# Bridge_H.net
KiCad netlist of a schematic drawn in Altium Designer
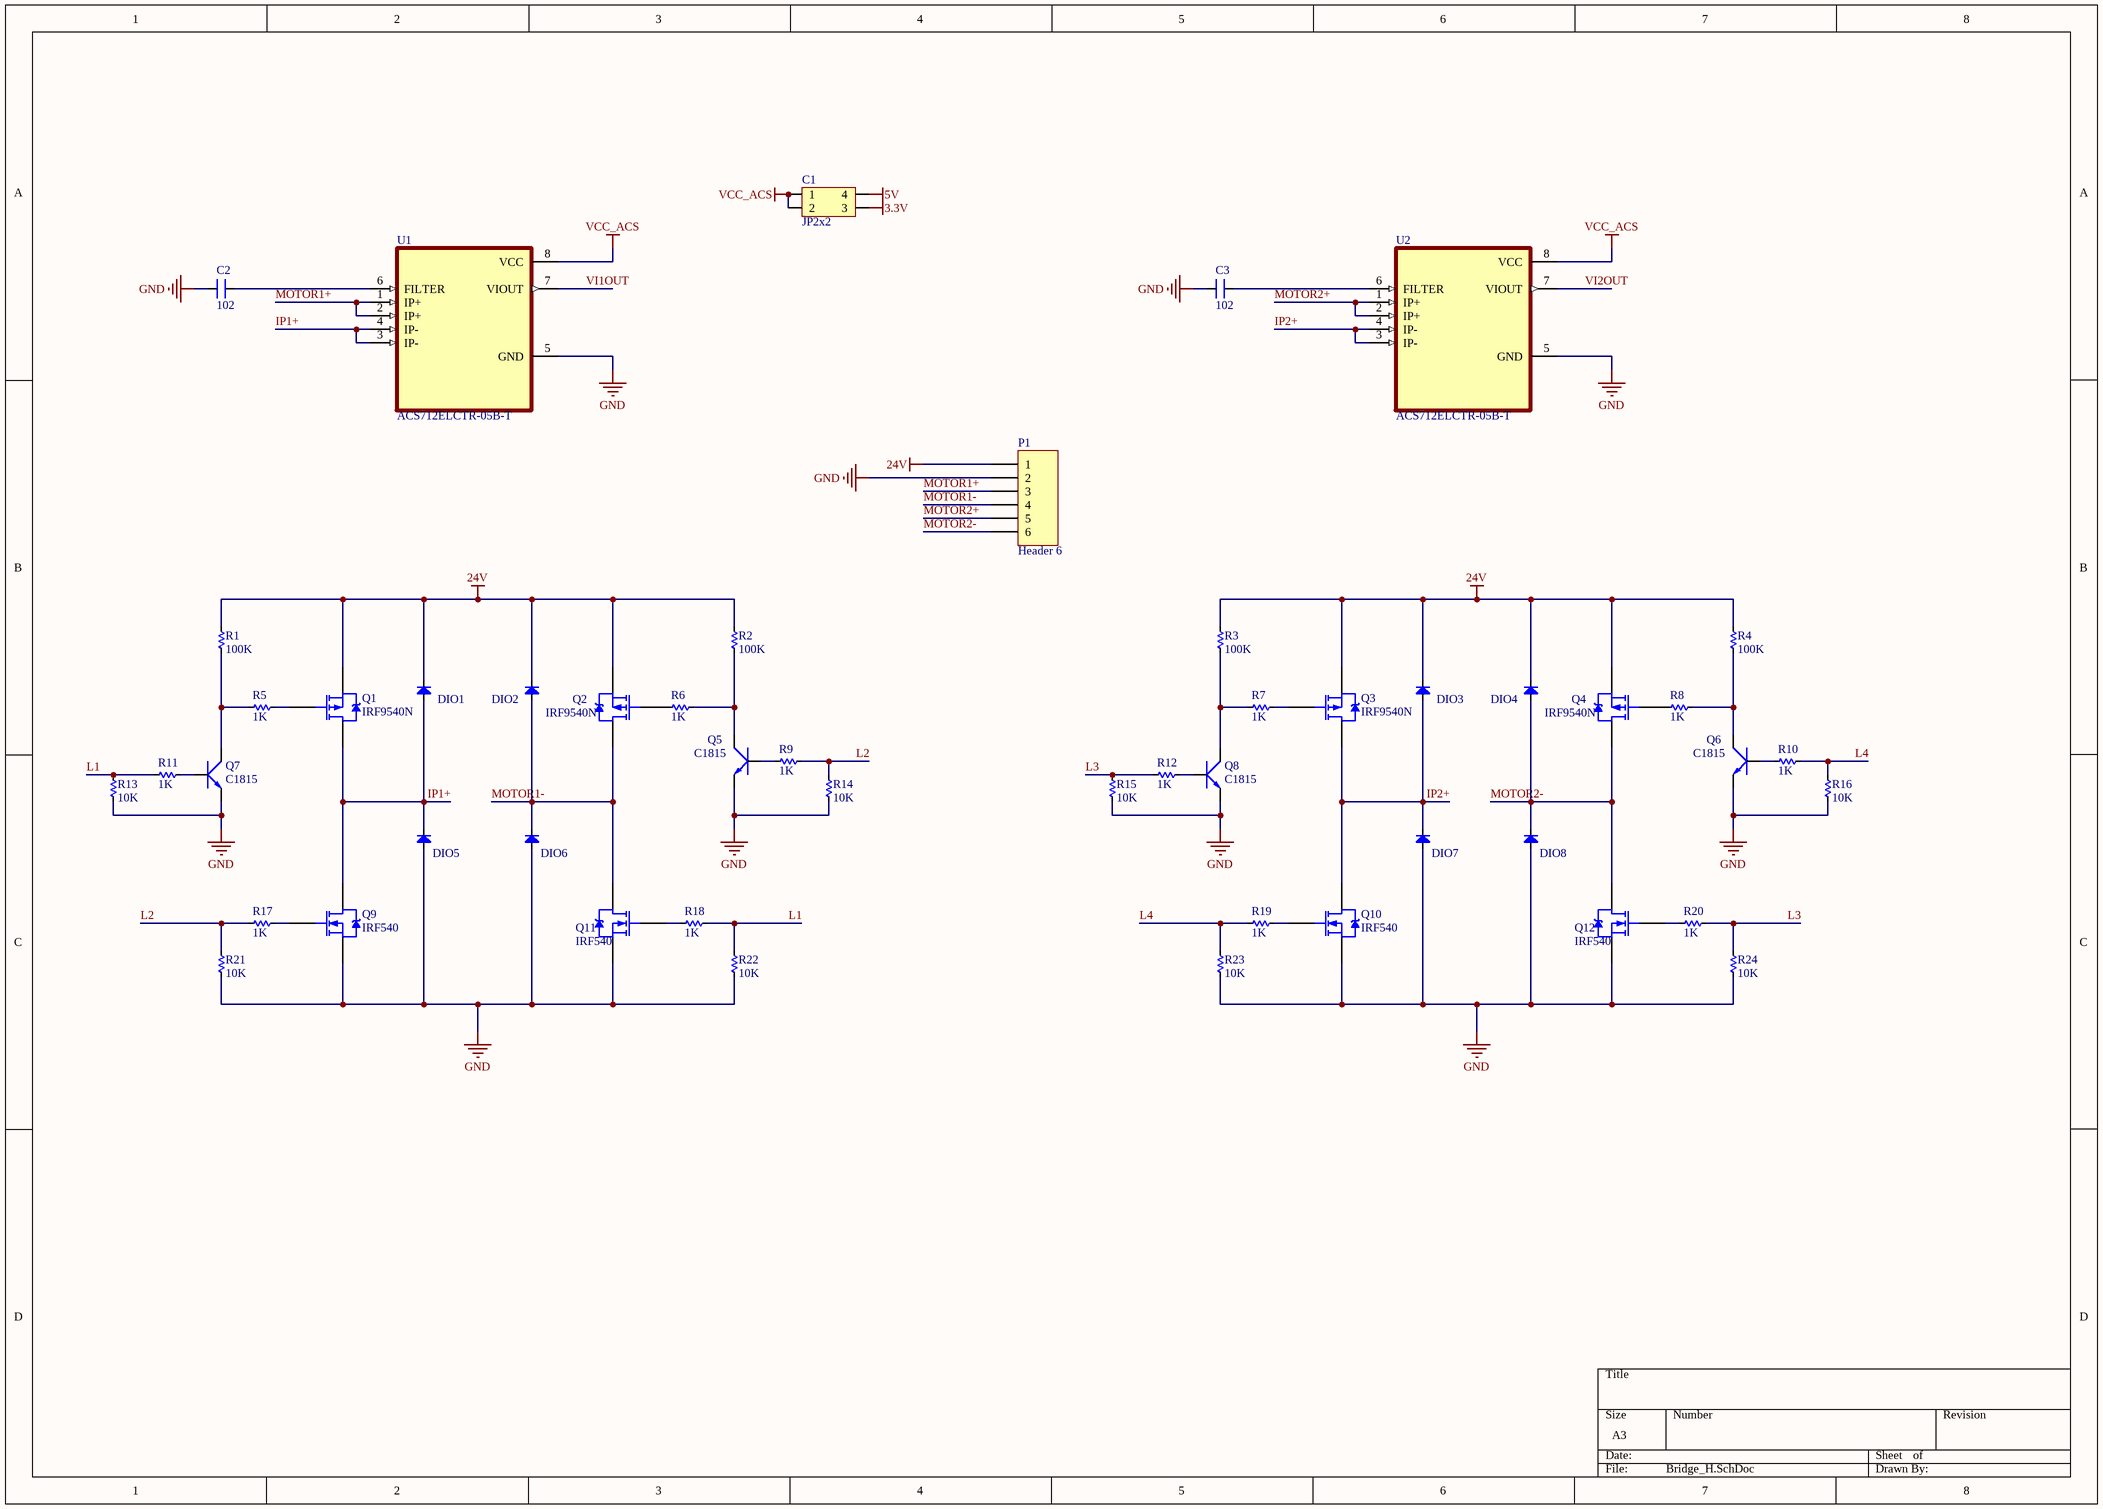
[diagram p0: Bridge_H.SchDoc]

(export (version "E")
  (design (tool "Eeschema 10.0.6"))
  (components
    (comp (ref "C1")
      (value "JP2x2")
      (footprint "JP2-D2T")
      (description "WR-PHD 2.54 mm Dual Socket Header")
      (fields
        (field (name "MANUFACTURER") "Würth Elektronik eiSos GmbH")
        (field (name "PARTNO") "61300421821")
        (field (name "CREATED BY") "Karrer Zheng")
      )
      (libsource (lib "LIBRARY") (part "JP2x2"))
    )
    (comp (ref "C2")
      (value "102")
      (footprint "SM-CAP-0805")
      (fields (field (name "DESIGNED BY") "VanDungEvn"))
      (libsource (lib "electronicvn-library1") (part "CN"))
    )
    (comp (ref "C3")
      (value "102")
      (footprint "SM-CAP-0805")
      (fields (field (name "DESIGNED BY") "VanDungEvn"))
      (libsource (lib "electronicvn-library1") (part "CN"))
    )
    (comp (ref "DIO1")
      (value "Diode SMD")
      (footprint "DIO-SMD-106")
      (description "Default Diode")
      (fields (field (name "PUBLISHER") "Altium Limited"))
      (libsource (lib "LIBRARY") (part "Diode SMD"))
    )
    (comp (ref "DIO2")
      (value "Diode SMD")
      (footprint "DIO-SMD-106")
      (description "Default Diode")
      (fields (field (name "PUBLISHER") "Altium Limited"))
      (libsource (lib "LIBRARY") (part "Diode SMD"))
    )
    (comp (ref "DIO3")
      (value "Diode SMD")
      (footprint "DIO-SMD-106")
      (description "Default Diode")
      (fields (field (name "PUBLISHER") "Altium Limited"))
      (libsource (lib "LIBRARY") (part "Diode SMD"))
    )
    (comp (ref "DIO4")
      (value "Diode SMD")
      (footprint "DIO-SMD-106")
      (description "Default Diode")
      (fields (field (name "PUBLISHER") "Altium Limited"))
      (libsource (lib "LIBRARY") (part "Diode SMD"))
    )
    (comp (ref "DIO5")
      (value "Diode SMD")
      (footprint "DIO-SMD-106")
      (description "Default Diode")
      (fields (field (name "PUBLISHER") "Altium Limited"))
      (libsource (lib "LIBRARY") (part "Diode SMD"))
    )
    (comp (ref "DIO6")
      (value "Diode SMD")
      (footprint "DIO-SMD-106")
      (description "Default Diode")
      (fields (field (name "PUBLISHER") "Altium Limited"))
      (libsource (lib "LIBRARY") (part "Diode SMD"))
    )
    (comp (ref "DIO7")
      (value "Diode SMD")
      (footprint "DIO-SMD-106")
      (description "Default Diode")
      (fields (field (name "PUBLISHER") "Altium Limited"))
      (libsource (lib "LIBRARY") (part "Diode SMD"))
    )
    (comp (ref "DIO8")
      (value "Diode SMD")
      (footprint "DIO-SMD-106")
      (description "Default Diode")
      (fields (field (name "PUBLISHER") "Altium Limited"))
      (libsource (lib "LIBRARY") (part "Diode SMD"))
    )
    (comp (ref "P1")
      (value "Header 6")
      (footprint "HED6T")
      (description "Header, 6-Pin")
      (fields (field (name "PUBLISHER") "Altium Limited"))
      (libsource (lib "LIBTanCN") (part "Header 6"))
    )
    (comp (ref "Q1")
      (value "IRF9540N")
      (footprint "TO-220AB")
      (description "HEXFET Power MOSFET")
      (fields (field (name "PUBLISHER") "Altium Limited"))
      (libsource (lib "IR Discrete MOSFET - Power") (part "IRF9540N"))
    )
    (comp (ref "Q2")
      (value "IRF9540N")
      (footprint "TO-220AB")
      (description "HEXFET Power MOSFET")
      (fields (field (name "PUBLISHER") "Altium Limited"))
      (libsource (lib "IR Discrete MOSFET - Power") (part "IRF9540N"))
    )
    (comp (ref "Q3")
      (value "IRF9540N")
      (footprint "TO-220AB")
      (description "HEXFET Power MOSFET")
      (fields (field (name "PUBLISHER") "Altium Limited"))
      (libsource (lib "IR Discrete MOSFET - Power") (part "IRF9540N"))
    )
    (comp (ref "Q4")
      (value "IRF9540N")
      (footprint "TO-220AB")
      (description "HEXFET Power MOSFET")
      (fields (field (name "PUBLISHER") "Altium Limited"))
      (libsource (lib "IR Discrete MOSFET - Power") (part "IRF9540N"))
    )
    (comp (ref "Q5")
      (value "C1815")
      (footprint "SOT23B")
      (description "NPN 600mW, ECB")
      (libsource (lib "electronicvn-library1") (part "C1815"))
    )
    (comp (ref "Q6")
      (value "C1815")
      (footprint "SOT23B")
      (description "NPN 600mW, ECB")
      (libsource (lib "electronicvn-library1") (part "C1815"))
    )
    (comp (ref "Q7")
      (value "C1815")
      (footprint "SOT23B")
      (description "NPN 600mW, ECB")
      (libsource (lib "electronicvn-library1") (part "C1815"))
    )
    (comp (ref "Q8")
      (value "C1815")
      (footprint "SOT23B")
      (description "NPN 600mW, ECB")
      (libsource (lib "electronicvn-library1") (part "C1815"))
    )
    (comp (ref "Q9")
      (value "IRF540")
      (footprint "TO-220AB")
      (description "HEXFET N-Channel Power MOSFET")
      (fields (field (name "PUBLISHER") "Altium Limited"))
      (libsource (lib "IR Discrete MOSFET - Power") (part "IRF540"))
    )
    (comp (ref "Q10")
      (value "IRF540")
      (footprint "TO-220AB")
      (description "HEXFET N-Channel Power MOSFET")
      (fields (field (name "PUBLISHER") "Altium Limited"))
      (libsource (lib "IR Discrete MOSFET - Power") (part "IRF540"))
    )
    (comp (ref "Q11")
      (value "IRF540")
      (footprint "TO-220AB")
      (description "HEXFET N-Channel Power MOSFET")
      (fields (field (name "PUBLISHER") "Altium Limited"))
      (libsource (lib "IR Discrete MOSFET - Power") (part "IRF540"))
    )
    (comp (ref "Q12")
      (value "IRF540")
      (footprint "TO-220AB")
      (description "HEXFET N-Channel Power MOSFET")
      (fields (field (name "PUBLISHER") "Altium Limited"))
      (libsource (lib "IR Discrete MOSFET - Power") (part "IRF540"))
    )
    (comp (ref "R1")
      (value "100K")
      (footprint "RES-SMD-0805")
      (description "Resistor")
      (fields
        (field (name "MANUFACTURER") "Generic Components")
        (field (name "PUBLISHER") "Altium Hobart Technology Centre")
      )
      (libsource (lib "LIBRARY") (part "Res-SMD"))
    )
    (comp (ref "R2")
      (value "100K")
      (footprint "RES-SMD-0805")
      (description "Resistor")
      (fields
        (field (name "MANUFACTURER") "Generic Components")
        (field (name "PUBLISHER") "Altium Hobart Technology Centre")
      )
      (libsource (lib "LIBRARY") (part "Res-SMD"))
    )
    (comp (ref "R3")
      (value "100K")
      (footprint "RES-SMD-0805")
      (description "Resistor")
      (fields
        (field (name "MANUFACTURER") "Generic Components")
        (field (name "PUBLISHER") "Altium Hobart Technology Centre")
      )
      (libsource (lib "LIBRARY") (part "Res-SMD"))
    )
    (comp (ref "R4")
      (value "100K")
      (footprint "RES-SMD-0805")
      (description "Resistor")
      (fields
        (field (name "MANUFACTURER") "Generic Components")
        (field (name "PUBLISHER") "Altium Hobart Technology Centre")
      )
      (libsource (lib "LIBRARY") (part "Res-SMD"))
    )
    (comp (ref "R5")
      (value "1K")
      (footprint "RES-SMD-0805")
      (description "Resistor")
      (fields
        (field (name "MANUFACTURER") "Generic Components")
        (field (name "PUBLISHER") "Altium Hobart Technology Centre")
      )
      (libsource (lib "LIBRARY") (part "Res-SMD"))
    )
    (comp (ref "R6")
      (value "1K")
      (footprint "RES-SMD-0805")
      (description "Resistor")
      (fields
        (field (name "MANUFACTURER") "Generic Components")
        (field (name "PUBLISHER") "Altium Hobart Technology Centre")
      )
      (libsource (lib "LIBRARY") (part "Res-SMD"))
    )
    (comp (ref "R7")
      (value "1K")
      (footprint "RES-SMD-0805")
      (description "Resistor")
      (fields
        (field (name "MANUFACTURER") "Generic Components")
        (field (name "PUBLISHER") "Altium Hobart Technology Centre")
      )
      (libsource (lib "LIBRARY") (part "Res-SMD"))
    )
    (comp (ref "R8")
      (value "1K")
      (footprint "RES-SMD-0805")
      (description "Resistor")
      (fields
        (field (name "MANUFACTURER") "Generic Components")
        (field (name "PUBLISHER") "Altium Hobart Technology Centre")
      )
      (libsource (lib "LIBRARY") (part "Res-SMD"))
    )
    (comp (ref "R9")
      (value "1K")
      (footprint "RES-SMD-0805")
      (description "Resistor")
      (fields
        (field (name "MANUFACTURER") "Generic Components")
        (field (name "PUBLISHER") "Altium Hobart Technology Centre")
      )
      (libsource (lib "LIBRARY") (part "Res-SMD"))
    )
    (comp (ref "R10")
      (value "1K")
      (footprint "RES-SMD-0805")
      (description "Resistor")
      (fields
        (field (name "MANUFACTURER") "Generic Components")
        (field (name "PUBLISHER") "Altium Hobart Technology Centre")
      )
      (libsource (lib "LIBRARY") (part "Res-SMD"))
    )
    (comp (ref "R11")
      (value "1K")
      (footprint "RES-SMD-0805")
      (description "Resistor")
      (fields
        (field (name "MANUFACTURER") "Generic Components")
        (field (name "PUBLISHER") "Altium Hobart Technology Centre")
      )
      (libsource (lib "LIBRARY") (part "Res-SMD"))
    )
    (comp (ref "R12")
      (value "1K")
      (footprint "RES-SMD-0805")
      (description "Resistor")
      (fields
        (field (name "MANUFACTURER") "Generic Components")
        (field (name "PUBLISHER") "Altium Hobart Technology Centre")
      )
      (libsource (lib "LIBRARY") (part "Res-SMD"))
    )
    (comp (ref "R13")
      (value "10K")
      (footprint "RES-SMD-0805")
      (description "Resistor")
      (fields
        (field (name "MANUFACTURER") "Generic Components")
        (field (name "PUBLISHER") "Altium Hobart Technology Centre")
      )
      (libsource (lib "LIBRARY") (part "Res-SMD"))
    )
    (comp (ref "R14")
      (value "10K")
      (footprint "RES-SMD-0805")
      (description "Resistor")
      (fields
        (field (name "MANUFACTURER") "Generic Components")
        (field (name "PUBLISHER") "Altium Hobart Technology Centre")
      )
      (libsource (lib "LIBRARY") (part "Res-SMD"))
    )
    (comp (ref "R15")
      (value "10K")
      (footprint "RES-SMD-0805")
      (description "Resistor")
      (fields
        (field (name "MANUFACTURER") "Generic Components")
        (field (name "PUBLISHER") "Altium Hobart Technology Centre")
      )
      (libsource (lib "LIBRARY") (part "Res-SMD"))
    )
    (comp (ref "R16")
      (value "10K")
      (footprint "RES-SMD-0805")
      (description "Resistor")
      (fields
        (field (name "MANUFACTURER") "Generic Components")
        (field (name "PUBLISHER") "Altium Hobart Technology Centre")
      )
      (libsource (lib "LIBRARY") (part "Res-SMD"))
    )
    (comp (ref "R17")
      (value "1K")
      (footprint "RES-SMD-0805")
      (description "Resistor")
      (fields
        (field (name "MANUFACTURER") "Generic Components")
        (field (name "PUBLISHER") "Altium Hobart Technology Centre")
      )
      (libsource (lib "LIBRARY") (part "Res-SMD"))
    )
    (comp (ref "R18")
      (value "1K")
      (footprint "RES-SMD-0805")
      (description "Resistor")
      (fields
        (field (name "MANUFACTURER") "Generic Components")
        (field (name "PUBLISHER") "Altium Hobart Technology Centre")
      )
      (libsource (lib "LIBRARY") (part "Res-SMD"))
    )
    (comp (ref "R19")
      (value "1K")
      (footprint "RES-SMD-0805")
      (description "Resistor")
      (fields
        (field (name "MANUFACTURER") "Generic Components")
        (field (name "PUBLISHER") "Altium Hobart Technology Centre")
      )
      (libsource (lib "LIBRARY") (part "Res-SMD"))
    )
    (comp (ref "R20")
      (value "1K")
      (footprint "RES-SMD-0805")
      (description "Resistor")
      (fields
        (field (name "MANUFACTURER") "Generic Components")
        (field (name "PUBLISHER") "Altium Hobart Technology Centre")
      )
      (libsource (lib "LIBRARY") (part "Res-SMD"))
    )
    (comp (ref "R21")
      (value "10K")
      (footprint "RES-SMD-0805")
      (description "Resistor")
      (fields
        (field (name "MANUFACTURER") "Generic Components")
        (field (name "PUBLISHER") "Altium Hobart Technology Centre")
      )
      (libsource (lib "LIBRARY") (part "Res-SMD"))
    )
    (comp (ref "R22")
      (value "10K")
      (footprint "RES-SMD-0805")
      (description "Resistor")
      (fields
        (field (name "MANUFACTURER") "Generic Components")
        (field (name "PUBLISHER") "Altium Hobart Technology Centre")
      )
      (libsource (lib "LIBRARY") (part "Res-SMD"))
    )
    (comp (ref "R23")
      (value "10K")
      (footprint "RES-SMD-0805")
      (description "Resistor")
      (fields
        (field (name "MANUFACTURER") "Generic Components")
        (field (name "PUBLISHER") "Altium Hobart Technology Centre")
      )
      (libsource (lib "LIBRARY") (part "Res-SMD"))
    )
    (comp (ref "R24")
      (value "10K")
      (footprint "RES-SMD-0805")
      (description "Resistor")
      (fields
        (field (name "MANUFACTURER") "Generic Components")
        (field (name "PUBLISHER") "Altium Hobart Technology Centre")
      )
      (libsource (lib "LIBRARY") (part "Res-SMD"))
    )
    (comp (ref "U1")
      (value "ACS712ELCTR-05B-T")
      (footprint "SOIC127P600X175-8N")
      (description "Current Sensor 5A 1 Channel Hall Effect, Open Loop Bidirectional 8-SOIC _0.154, 3.90mm Width_")
      (fields
        (field (name "DIGI-KEY_PART_NUMBER") "620-1189-1-ND")
        (field (name "MF") "Allegro MicroSystems LLC")
      )
      (libsource (lib "ACS712ELCTR-05B-T") (part "ACS712ELCTR-05B-T"))
    )
    (comp (ref "U2")
      (value "ACS712ELCTR-05B-T")
      (footprint "SOIC127P600X175-8N")
      (description "Current Sensor 5A 1 Channel Hall Effect, Open Loop Bidirectional 8-SOIC _0.154, 3.90mm Width_")
      (fields
        (field (name "DIGI-KEY_PART_NUMBER") "620-1189-1-ND")
        (field (name "MF") "Allegro MicroSystems LLC")
      )
      (libsource (lib "ACS712ELCTR-05B-T") (part "ACS712ELCTR-05B-T"))
    )
  )
  (nets
    (net (code "1") (name "/IP1+") (class "Default")
      (node (ref "DIO1") (pin "1") (pinfunction "A_1") (pintype "passive"))
      (node (ref "DIO5") (pin "2") (pinfunction "K_2") (pintype "passive"))
      (node (ref "Q1") (pin "2") (pinfunction "D_2") (pintype "passive"))
      (node (ref "Q9") (pin "2") (pinfunction "D_2") (pintype "passive"))
      (node (ref "U1") (pin "3") (pinfunction "IP-_3") (pintype "input"))
      (node (ref "U1") (pin "4") (pinfunction "IP-_4") (pintype "input"))
    )
    (net (code "2") (name "/IP2+") (class "Default")
      (node (ref "DIO3") (pin "1") (pinfunction "A_1") (pintype "passive"))
      (node (ref "DIO7") (pin "2") (pinfunction "K_2") (pintype "passive"))
      (node (ref "Q10") (pin "2") (pinfunction "D_2") (pintype "passive"))
      (node (ref "Q3") (pin "2") (pinfunction "D_2") (pintype "passive"))
      (node (ref "U2") (pin "3") (pinfunction "IP-_3") (pintype "input"))
      (node (ref "U2") (pin "4") (pinfunction "IP-_4") (pintype "input"))
    )
    (net (code "3") (name "/L1") (class "Default")
      (node (ref "R11") (pin "2") (pinfunction "2_2") (pintype "passive"))
      (node (ref "R13") (pin "1") (pinfunction "1_1") (pintype "passive"))
      (node (ref "R18") (pin "1") (pinfunction "1_1") (pintype "passive"))
      (node (ref "R22") (pin "1") (pinfunction "1_1") (pintype "passive"))
    )
    (net (code "4") (name "/L2") (class "Default")
      (node (ref "R14") (pin "1") (pinfunction "1_1") (pintype "passive"))
      (node (ref "R17") (pin "2") (pinfunction "2_2") (pintype "passive"))
      (node (ref "R21") (pin "1") (pinfunction "1_1") (pintype "passive"))
      (node (ref "R9") (pin "1") (pinfunction "1_1") (pintype "passive"))
    )
    (net (code "5") (name "/L3") (class "Default")
      (node (ref "R12") (pin "2") (pinfunction "2_2") (pintype "passive"))
      (node (ref "R15") (pin "1") (pinfunction "1_1") (pintype "passive"))
      (node (ref "R20") (pin "1") (pinfunction "1_1") (pintype "passive"))
      (node (ref "R24") (pin "1") (pinfunction "1_1") (pintype "passive"))
    )
    (net (code "6") (name "/L4") (class "Default")
      (node (ref "R10") (pin "1") (pinfunction "1_1") (pintype "passive"))
      (node (ref "R16") (pin "1") (pinfunction "1_1") (pintype "passive"))
      (node (ref "R19") (pin "2") (pinfunction "2_2") (pintype "passive"))
      (node (ref "R23") (pin "1") (pinfunction "1_1") (pintype "passive"))
    )
    (net (code "7") (name "/MOTOR1+") (class "Default")
      (node (ref "P1") (pin "3") (pinfunction "3_3") (pintype "passive"))
      (node (ref "U1") (pin "1") (pinfunction "IP+_1") (pintype "input"))
      (node (ref "U1") (pin "2") (pinfunction "IP+_2") (pintype "input"))
    )
    (net (code "8") (name "/MOTOR1-") (class "Default")
      (node (ref "DIO2") (pin "1") (pinfunction "A_1") (pintype "passive"))
      (node (ref "DIO6") (pin "2") (pinfunction "K_2") (pintype "passive"))
      (node (ref "P1") (pin "4") (pinfunction "4_4") (pintype "passive"))
      (node (ref "Q11") (pin "2") (pinfunction "D_2") (pintype "passive"))
      (node (ref "Q2") (pin "2") (pinfunction "D_2") (pintype "passive"))
    )
    (net (code "9") (name "/MOTOR2+") (class "Default")
      (node (ref "P1") (pin "5") (pinfunction "5_5") (pintype "passive"))
      (node (ref "U2") (pin "1") (pinfunction "IP+_1") (pintype "input"))
      (node (ref "U2") (pin "2") (pinfunction "IP+_2") (pintype "input"))
    )
    (net (code "10") (name "/MOTOR2-") (class "Default")
      (node (ref "DIO4") (pin "1") (pinfunction "A_1") (pintype "passive"))
      (node (ref "DIO8") (pin "2") (pinfunction "K_2") (pintype "passive"))
      (node (ref "P1") (pin "6") (pinfunction "6_6") (pintype "passive"))
      (node (ref "Q12") (pin "2") (pinfunction "D_2") (pintype "passive"))
      (node (ref "Q4") (pin "2") (pinfunction "D_2") (pintype "passive"))
    )
    (net (code "11") (name "/VI1OUT") (class "Default")
      (node (ref "U1") (pin "7") (pinfunction "VIOUT_7") (pintype "output"))
    )
    (net (code "12") (name "/VI2OUT") (class "Default")
      (node (ref "U2") (pin "7") (pinfunction "VIOUT_7") (pintype "output"))
    )
    (net (code "13") (name "3.3V") (class "Default")
      (node (ref "C1") (pin "3") (pinfunction "3_3") (pintype "passive"))
    )
    (net (code "14") (name "5V") (class "Default")
      (node (ref "C1") (pin "4") (pinfunction "4_4") (pintype "passive"))
    )
    (net (code "15") (name "24V") (class "Default")
      (node (ref "DIO1") (pin "2") (pinfunction "K_2") (pintype "passive"))
      (node (ref "DIO2") (pin "2") (pinfunction "K_2") (pintype "passive"))
      (node (ref "DIO3") (pin "2") (pinfunction "K_2") (pintype "passive"))
      (node (ref "DIO4") (pin "2") (pinfunction "K_2") (pintype "passive"))
      (node (ref "P1") (pin "1") (pinfunction "1_1") (pintype "passive"))
      (node (ref "Q1") (pin "3") (pinfunction "S_3") (pintype "passive"))
      (node (ref "Q2") (pin "3") (pinfunction "S_3") (pintype "passive"))
      (node (ref "Q3") (pin "3") (pinfunction "S_3") (pintype "passive"))
      (node (ref "Q4") (pin "3") (pinfunction "S_3") (pintype "passive"))
      (node (ref "R1") (pin "1") (pinfunction "1_1") (pintype "passive"))
      (node (ref "R2") (pin "1") (pinfunction "1_1") (pintype "passive"))
      (node (ref "R3") (pin "1") (pinfunction "1_1") (pintype "passive"))
      (node (ref "R4") (pin "1") (pinfunction "1_1") (pintype "passive"))
    )
    (net (code "16") (name "GND") (class "Default")
      (node (ref "C2") (pin "1") (pinfunction "1_1") (pintype "passive"))
      (node (ref "C3") (pin "1") (pinfunction "1_1") (pintype "passive"))
      (node (ref "DIO5") (pin "1") (pinfunction "A_1") (pintype "passive"))
      (node (ref "DIO6") (pin "1") (pinfunction "A_1") (pintype "passive"))
      (node (ref "DIO7") (pin "1") (pinfunction "A_1") (pintype "passive"))
      (node (ref "DIO8") (pin "1") (pinfunction "A_1") (pintype "passive"))
      (node (ref "P1") (pin "2") (pinfunction "2_2") (pintype "passive"))
      (node (ref "Q10") (pin "3") (pinfunction "S_3") (pintype "passive"))
      (node (ref "Q11") (pin "3") (pinfunction "S_3") (pintype "passive"))
      (node (ref "Q12") (pin "3") (pinfunction "S_3") (pintype "passive"))
      (node (ref "Q5") (pin "1") (pinfunction "E_1") (pintype "passive"))
      (node (ref "Q6") (pin "1") (pinfunction "E_1") (pintype "passive"))
      (node (ref "Q7") (pin "1") (pinfunction "E_1") (pintype "passive"))
      (node (ref "Q8") (pin "1") (pinfunction "E_1") (pintype "passive"))
      (node (ref "Q9") (pin "3") (pinfunction "S_3") (pintype "passive"))
      (node (ref "R13") (pin "2") (pinfunction "2_2") (pintype "passive"))
      (node (ref "R14") (pin "2") (pinfunction "2_2") (pintype "passive"))
      (node (ref "R15") (pin "2") (pinfunction "2_2") (pintype "passive"))
      (node (ref "R16") (pin "2") (pinfunction "2_2") (pintype "passive"))
      (node (ref "R21") (pin "2") (pinfunction "2_2") (pintype "passive"))
      (node (ref "R22") (pin "2") (pinfunction "2_2") (pintype "passive"))
      (node (ref "R23") (pin "2") (pinfunction "2_2") (pintype "passive"))
      (node (ref "R24") (pin "2") (pinfunction "2_2") (pintype "passive"))
      (node (ref "U1") (pin "5") (pinfunction "GND_5") (pintype "power_in"))
      (node (ref "U2") (pin "5") (pinfunction "GND_5") (pintype "power_in"))
    )
    (net (code "17") (name "Net-(Q1-G)") (class "Default")
      (node (ref "Q1") (pin "1") (pinfunction "G_1") (pintype "passive"))
      (node (ref "R5") (pin "2") (pinfunction "2_2") (pintype "passive"))
    )
    (net (code "18") (name "Net-(Q2-G)") (class "Default")
      (node (ref "Q2") (pin "1") (pinfunction "G_1") (pintype "passive"))
      (node (ref "R6") (pin "1") (pinfunction "1_1") (pintype "passive"))
    )
    (net (code "19") (name "Net-(Q3-G)") (class "Default")
      (node (ref "Q3") (pin "1") (pinfunction "G_1") (pintype "passive"))
      (node (ref "R7") (pin "2") (pinfunction "2_2") (pintype "passive"))
    )
    (net (code "20") (name "Net-(Q4-G)") (class "Default")
      (node (ref "Q4") (pin "1") (pinfunction "G_1") (pintype "passive"))
      (node (ref "R8") (pin "1") (pinfunction "1_1") (pintype "passive"))
    )
    (net (code "21") (name "Net-(Q5-B)") (class "Default")
      (node (ref "Q5") (pin "3") (pinfunction "B_3") (pintype "passive"))
      (node (ref "R9") (pin "2") (pinfunction "2_2") (pintype "passive"))
    )
    (net (code "22") (name "Net-(Q5-C)") (class "Default")
      (node (ref "Q5") (pin "2") (pinfunction "C_2") (pintype "passive"))
      (node (ref "R2") (pin "2") (pinfunction "2_2") (pintype "passive"))
      (node (ref "R6") (pin "2") (pinfunction "2_2") (pintype "passive"))
    )
    (net (code "23") (name "Net-(Q6-B)") (class "Default")
      (node (ref "Q6") (pin "3") (pinfunction "B_3") (pintype "passive"))
      (node (ref "R10") (pin "2") (pinfunction "2_2") (pintype "passive"))
    )
    (net (code "24") (name "Net-(Q6-C)") (class "Default")
      (node (ref "Q6") (pin "2") (pinfunction "C_2") (pintype "passive"))
      (node (ref "R4") (pin "2") (pinfunction "2_2") (pintype "passive"))
      (node (ref "R8") (pin "2") (pinfunction "2_2") (pintype "passive"))
    )
    (net (code "25") (name "Net-(Q7-B)") (class "Default")
      (node (ref "Q7") (pin "3") (pinfunction "B_3") (pintype "passive"))
      (node (ref "R11") (pin "1") (pinfunction "1_1") (pintype "passive"))
    )
    (net (code "26") (name "Net-(Q7-C)") (class "Default")
      (node (ref "Q7") (pin "2") (pinfunction "C_2") (pintype "passive"))
      (node (ref "R1") (pin "2") (pinfunction "2_2") (pintype "passive"))
      (node (ref "R5") (pin "1") (pinfunction "1_1") (pintype "passive"))
    )
    (net (code "27") (name "Net-(Q8-B)") (class "Default")
      (node (ref "Q8") (pin "3") (pinfunction "B_3") (pintype "passive"))
      (node (ref "R12") (pin "1") (pinfunction "1_1") (pintype "passive"))
    )
    (net (code "28") (name "Net-(Q8-C)") (class "Default")
      (node (ref "Q8") (pin "2") (pinfunction "C_2") (pintype "passive"))
      (node (ref "R3") (pin "2") (pinfunction "2_2") (pintype "passive"))
      (node (ref "R7") (pin "1") (pinfunction "1_1") (pintype "passive"))
    )
    (net (code "29") (name "Net-(Q9-G)") (class "Default")
      (node (ref "Q9") (pin "1") (pinfunction "G_1") (pintype "passive"))
      (node (ref "R17") (pin "1") (pinfunction "1_1") (pintype "passive"))
    )
    (net (code "30") (name "Net-(Q10-G)") (class "Default")
      (node (ref "Q10") (pin "1") (pinfunction "G_1") (pintype "passive"))
      (node (ref "R19") (pin "1") (pinfunction "1_1") (pintype "passive"))
    )
    (net (code "31") (name "Net-(Q11-G)") (class "Default")
      (node (ref "Q11") (pin "1") (pinfunction "G_1") (pintype "passive"))
      (node (ref "R18") (pin "2") (pinfunction "2_2") (pintype "passive"))
    )
    (net (code "32") (name "Net-(Q12-G)") (class "Default")
      (node (ref "Q12") (pin "1") (pinfunction "G_1") (pintype "passive"))
      (node (ref "R20") (pin "2") (pinfunction "2_2") (pintype "passive"))
    )
    (net (code "33") (name "Net-(U1-FILTER)") (class "Default")
      (node (ref "C2") (pin "2") (pinfunction "2_2") (pintype "passive"))
      (node (ref "U1") (pin "6") (pinfunction "FILTER_6") (pintype "input"))
    )
    (net (code "34") (name "Net-(U2-FILTER)") (class "Default")
      (node (ref "C3") (pin "2") (pinfunction "2_2") (pintype "passive"))
      (node (ref "U2") (pin "6") (pinfunction "FILTER_6") (pintype "input"))
    )
    (net (code "35") (name "VCC_ACS") (class "Default")
      (node (ref "C1") (pin "1") (pinfunction "1_1") (pintype "passive"))
      (node (ref "C1") (pin "2") (pinfunction "2_2") (pintype "passive"))
      (node (ref "U1") (pin "8") (pinfunction "VCC_8") (pintype "power_in"))
      (node (ref "U2") (pin "8") (pinfunction "VCC_8") (pintype "power_in"))
    )
  )
)
